# PCB-BI8-SE-C30.net
KiCad netlist of a schematic drawn in EAGLE
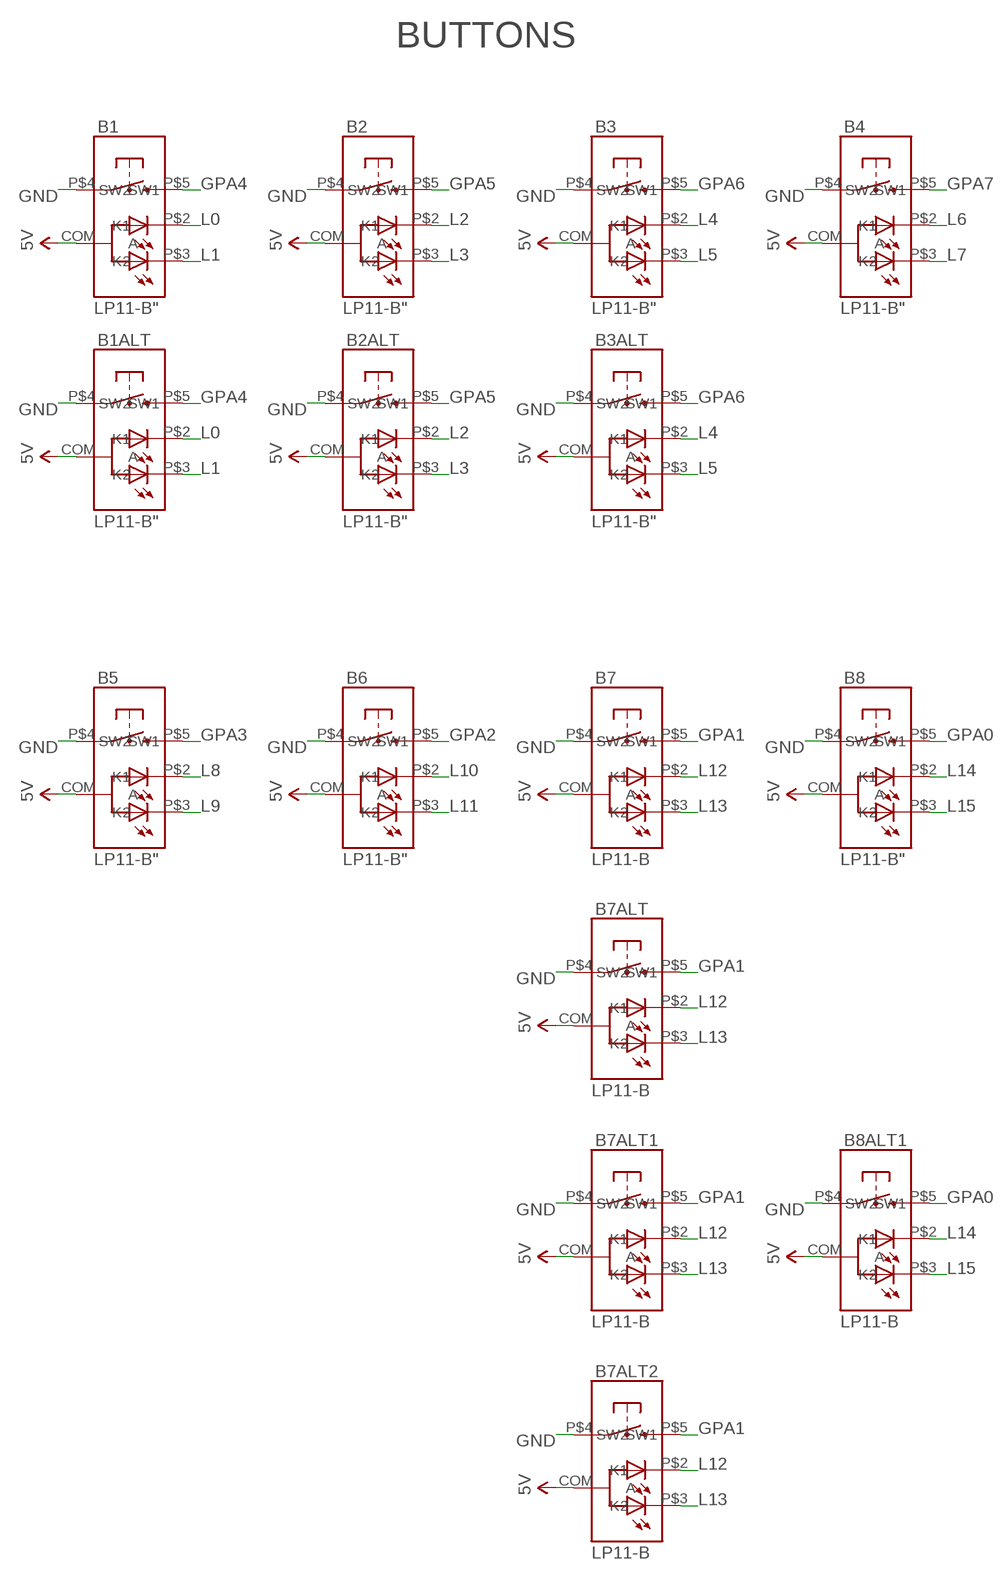
[diagram p0: schematic, sheet 1, part 1 of 2]
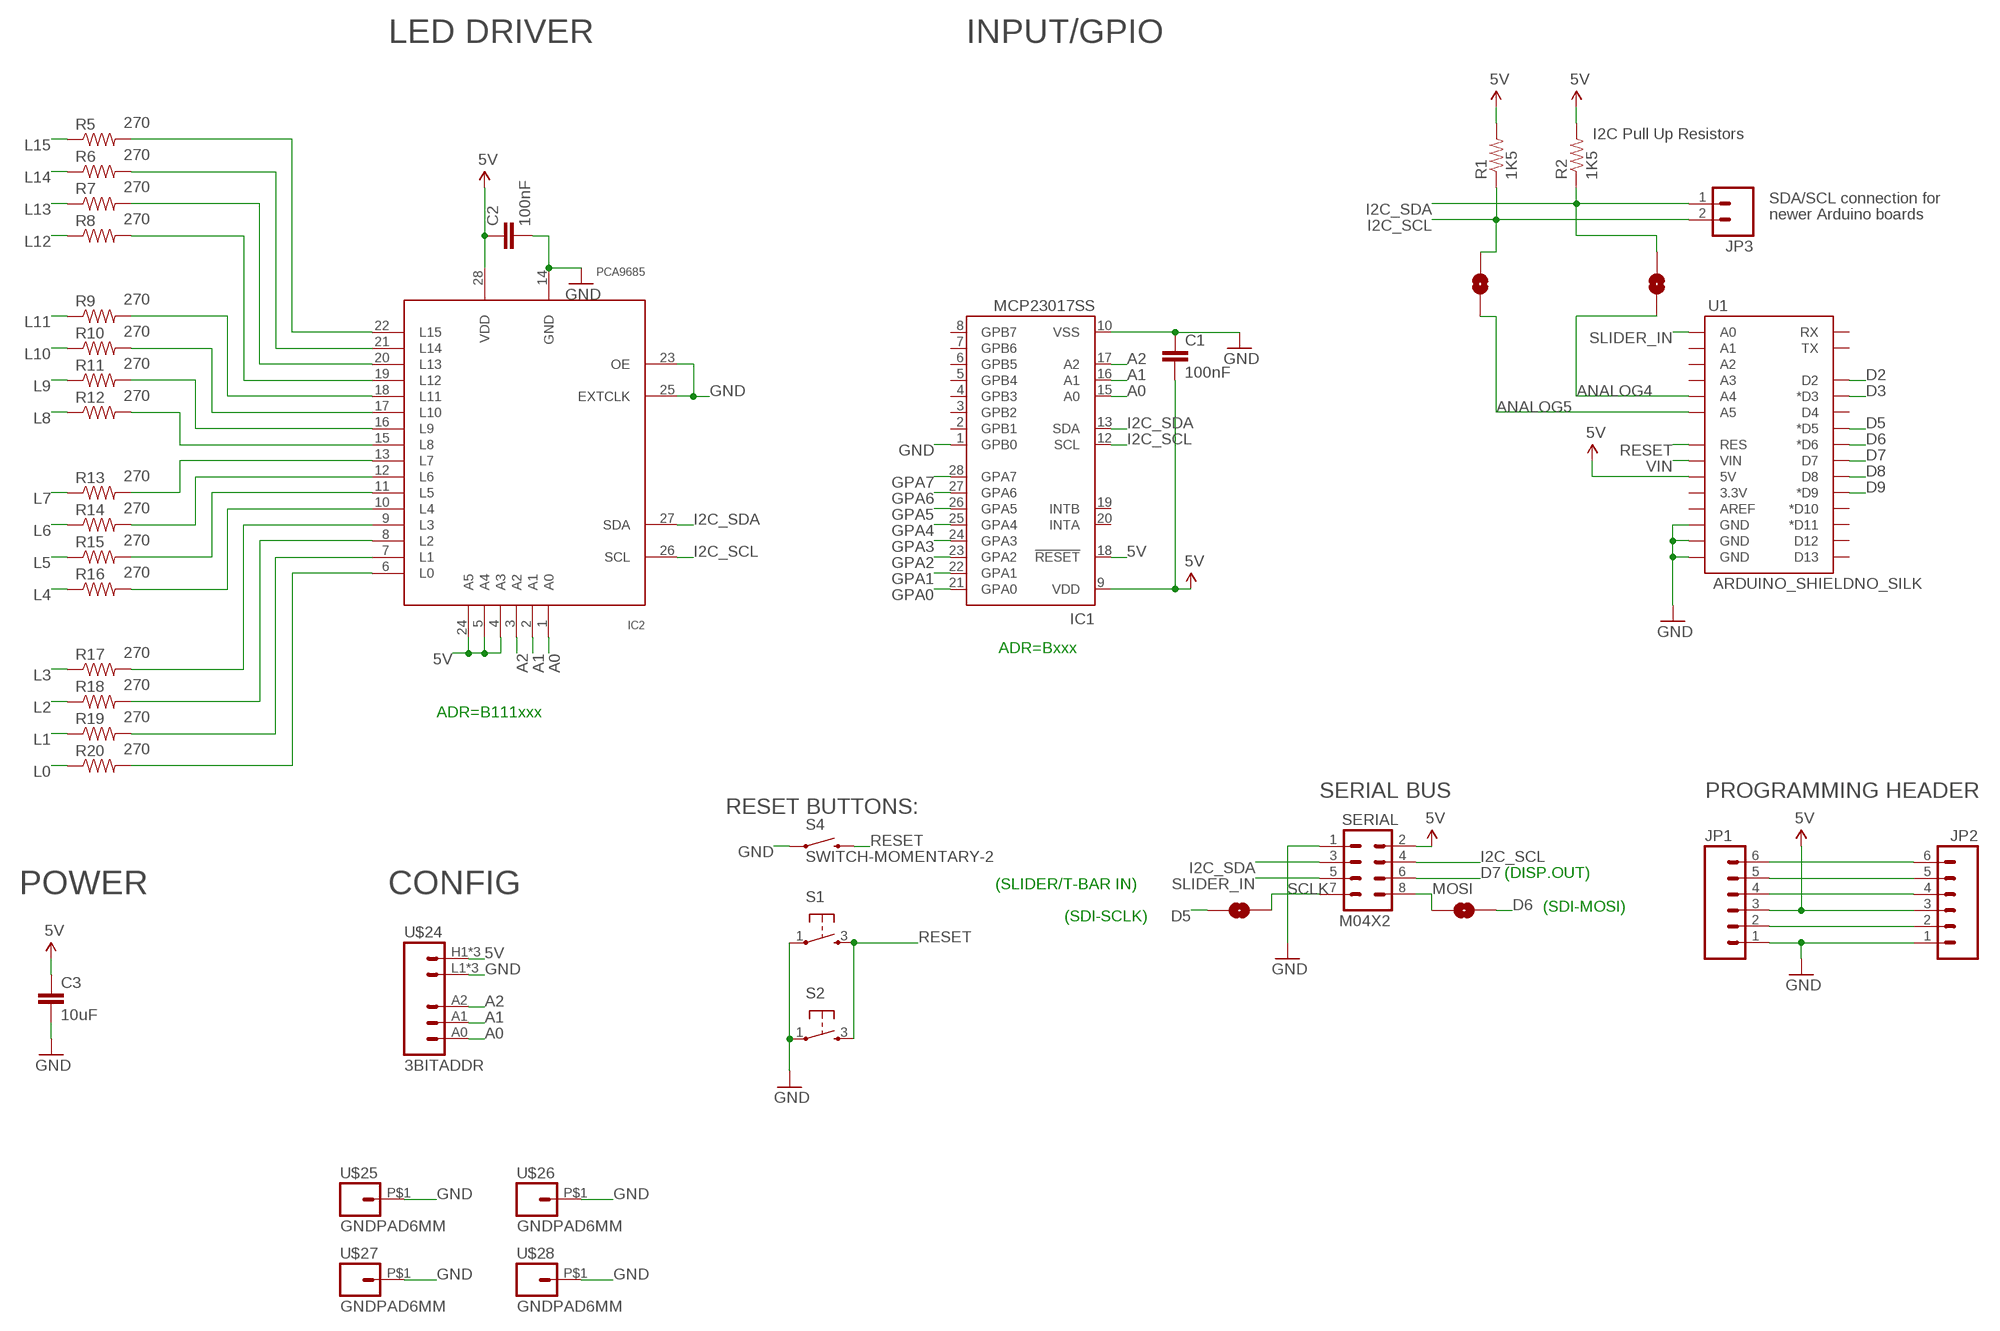
[diagram p1: schematic, sheet 1, part 2 of 2]

(export (version "E")
  (design (tool "Eeschema 10.0.6"))
  (components
    (comp (ref "B1")
      (value "LP11-B\"")
      (footprint "eagle-import:LP11")
      (libsource (lib "eagle-import") (part "LP11-B{dblquote}"))
    )
    (comp (ref "B1ALT")
      (value "LP11-B\"")
      (footprint "eagle-import:LP11")
      (libsource (lib "eagle-import") (part "LP11-B{dblquote}"))
    )
    (comp (ref "B2")
      (value "LP11-B\"")
      (footprint "eagle-import:LP11")
      (libsource (lib "eagle-import") (part "LP11-B{dblquote}"))
    )
    (comp (ref "B2ALT")
      (value "LP11-B\"")
      (footprint "eagle-import:LP11")
      (libsource (lib "eagle-import") (part "LP11-B{dblquote}"))
    )
    (comp (ref "B3")
      (value "LP11-B\"")
      (footprint "eagle-import:LP11")
      (libsource (lib "eagle-import") (part "LP11-B{dblquote}"))
    )
    (comp (ref "B3ALT")
      (value "LP11-B\"")
      (footprint "eagle-import:LP11")
      (libsource (lib "eagle-import") (part "LP11-B{dblquote}"))
    )
    (comp (ref "B4")
      (value "LP11-B\"")
      (footprint "eagle-import:LP11")
      (libsource (lib "eagle-import") (part "LP11-B{dblquote}"))
    )
    (comp (ref "B5")
      (value "LP11-B\"")
      (footprint "eagle-import:LP11")
      (libsource (lib "eagle-import") (part "LP11-B{dblquote}"))
    )
    (comp (ref "B6")
      (value "LP11-B\"")
      (footprint "eagle-import:LP11")
      (libsource (lib "eagle-import") (part "LP11-B{dblquote}"))
    )
    (comp (ref "B7")
      (value "LP11-B")
      (footprint "eagle-import:LP11_NOFIXHOLES")
      (libsource (lib "eagle-import") (part "LP11-B"))
    )
    (comp (ref "B7ALT")
      (value "LP11-B")
      (footprint "eagle-import:LP11_NOFIXHOLES")
      (libsource (lib "eagle-import") (part "LP11-B"))
    )
    (comp (ref "B7ALT1")
      (value "LP11-B")
      (footprint "eagle-import:LP11_NOFIXHOLES")
      (libsource (lib "eagle-import") (part "LP11-B"))
    )
    (comp (ref "B7ALT2")
      (value "LP11-B")
      (footprint "eagle-import:LP11_NOFIXHOLES")
      (libsource (lib "eagle-import") (part "LP11-B"))
    )
    (comp (ref "B8")
      (value "LP11-B\"")
      (footprint "eagle-import:LP11")
      (libsource (lib "eagle-import") (part "LP11-B{dblquote}"))
    )
    (comp (ref "B8ALT1")
      (value "LP11-B")
      (footprint "eagle-import:LP11_NOFIXHOLES")
      (libsource (lib "eagle-import") (part "LP11-B"))
    )
    (comp (ref "C1")
      (value "100nF")
      (footprint "eagle-import:0603-CAP")
      (libsource (lib "eagle-import") (part "CAP0603-CAP"))
    )
    (comp (ref "C2")
      (value "100nF")
      (footprint "eagle-import:0603-CAP")
      (libsource (lib "eagle-import") (part "CAP0603-CAP"))
    )
    (comp (ref "C3")
      (value "10uF")
      (footprint "eagle-import:0805")
      (libsource (lib "eagle-import") (part "CAP0805"))
    )
    (comp (ref "IC1")
      (value "MCP23017SS")
      (footprint "eagle-import:SSOP28")
      (fields
        (field (name "MF") "MICROCHIP")
        (field (name "MPN") "MCP23017-E/SS")
        (field (name "MPN_1") "MCP23017-E/SS")
        (field (name "OC_FARNELL") "1467674")
        (field (name "OC_NEWARK") "31K2960")
      )
      (libsource (lib "eagle-import") (part "MCP23017SS"))
    )
    (comp (ref "IC2")
      (value "PCA9685")
      (footprint "eagle-import:TSSOP28")
      (libsource (lib "eagle-import") (part "PCA9685"))
    )
    (comp (ref "JP1")
      (value "M06POLAR")
      (footprint "eagle-import:MOLEX-1X6")
      (libsource (lib "eagle-import") (part "M06POLAR"))
    )
    (comp (ref "JP2")
      (value "M06POLAR")
      (footprint "eagle-import:MOLEX-1X6")
      (libsource (lib "eagle-import") (part "M06POLAR"))
    )
    (comp (ref "JP3")
      (value "M02PTH")
      (footprint "eagle-import:1X02")
      (libsource (lib "eagle-import") (part "M02PTH"))
    )
    (comp (ref "MOSI->D6")
      (value "SOLDERJUMPERNC")
      (footprint "eagle-import:SJ_2S")
      (libsource (lib "eagle-import") (part "SOLDERJUMPERNC"))
    )
    (comp (ref "R1")
      (value "1K5")
      (footprint "eagle-import:0603-RES")
      (libsource (lib "eagle-import") (part "RESISTOR0603-RES"))
    )
    (comp (ref "R2")
      (value "1K5")
      (footprint "eagle-import:0603-RES")
      (libsource (lib "eagle-import") (part "RESISTOR0603-RES"))
    )
    (comp (ref "R5")
      (value "270")
      (footprint "eagle-import:0603-RES")
      (libsource (lib "eagle-import") (part "RESISTOR0603-RES"))
    )
    (comp (ref "R6")
      (value "270")
      (footprint "eagle-import:0603-RES")
      (libsource (lib "eagle-import") (part "RESISTOR0603-RES"))
    )
    (comp (ref "R7")
      (value "270")
      (footprint "eagle-import:0603-RES")
      (libsource (lib "eagle-import") (part "RESISTOR0603-RES"))
    )
    (comp (ref "R8")
      (value "270")
      (footprint "eagle-import:0603-RES")
      (libsource (lib "eagle-import") (part "RESISTOR0603-RES"))
    )
    (comp (ref "R9")
      (value "270")
      (footprint "eagle-import:0603-RES")
      (libsource (lib "eagle-import") (part "RESISTOR0603-RES"))
    )
    (comp (ref "R10")
      (value "270")
      (footprint "eagle-import:0603-RES")
      (libsource (lib "eagle-import") (part "RESISTOR0603-RES"))
    )
    (comp (ref "R11")
      (value "270")
      (footprint "eagle-import:0603-RES")
      (libsource (lib "eagle-import") (part "RESISTOR0603-RES"))
    )
    (comp (ref "R12")
      (value "270")
      (footprint "eagle-import:0603-RES")
      (libsource (lib "eagle-import") (part "RESISTOR0603-RES"))
    )
    (comp (ref "R13")
      (value "270")
      (footprint "eagle-import:0603-RES")
      (libsource (lib "eagle-import") (part "RESISTOR0603-RES"))
    )
    (comp (ref "R14")
      (value "270")
      (footprint "eagle-import:0603-RES")
      (libsource (lib "eagle-import") (part "RESISTOR0603-RES"))
    )
    (comp (ref "R15")
      (value "270")
      (footprint "eagle-import:0603-RES")
      (libsource (lib "eagle-import") (part "RESISTOR0603-RES"))
    )
    (comp (ref "R16")
      (value "270")
      (footprint "eagle-import:0603-RES")
      (libsource (lib "eagle-import") (part "RESISTOR0603-RES"))
    )
    (comp (ref "R17")
      (value "270")
      (footprint "eagle-import:0603-RES")
      (libsource (lib "eagle-import") (part "RESISTOR0603-RES"))
    )
    (comp (ref "R18")
      (value "270")
      (footprint "eagle-import:0603-RES")
      (libsource (lib "eagle-import") (part "RESISTOR0603-RES"))
    )
    (comp (ref "R19")
      (value "270")
      (footprint "eagle-import:0603-RES")
      (libsource (lib "eagle-import") (part "RESISTOR0603-RES"))
    )
    (comp (ref "R20")
      (value "270")
      (footprint "eagle-import:0603-RES")
      (libsource (lib "eagle-import") (part "RESISTOR0603-RES"))
    )
    (comp (ref "S1")
      (value "TAC_SWITCH")
      (footprint "eagle-import:PUSHBUTTON")
      (libsource (lib "eagle-import") (part "TAC_SWITCH"))
    )
    (comp (ref "S2")
      (value "TAC_SWITCH")
      (footprint "eagle-import:PUSHBUTTON")
      (libsource (lib "eagle-import") (part "TAC_SWITCH"))
    )
    (comp (ref "S3->A2")
      (value "SOLDERJUMPERNC")
      (footprint "eagle-import:SJ_2S")
      (libsource (lib "eagle-import") (part "SOLDERJUMPERNC"))
    )
    (comp (ref "S3->A3")
      (value "SOLDERJUMPERNC")
      (footprint "eagle-import:SJ_2S")
      (libsource (lib "eagle-import") (part "SOLDERJUMPERNC"))
    )
    (comp (ref "S4")
      (value "SWITCH-MOMENTARY-2")
      (footprint "eagle-import:TACTILE_SWITCH_TALL")
      (libsource (lib "eagle-import") (part "SWITCH-MOMENTARY-2"))
    )
    (comp (ref "SCLK->D5")
      (value "SOLDERJUMPERNC")
      (footprint "eagle-import:SJ_2S")
      (libsource (lib "eagle-import") (part "SOLDERJUMPERNC"))
    )
    (comp (ref "SERIAL")
      (value "M04X2")
      (footprint "eagle-import:2X4")
      (libsource (lib "eagle-import") (part "M04X2"))
    )
    (comp (ref "U$24")
      (value "3BITADDR")
      (footprint "eagle-import:3BITADDR")
      (libsource (lib "eagle-import") (part "3BITADDR"))
    )
    (comp (ref "U$25")
      (value "GNDPAD6MM")
      (footprint "eagle-import:3.2MMPAD6MM")
      (libsource (lib "eagle-import") (part "GNDPAD6MM"))
    )
    (comp (ref "U$26")
      (value "GNDPAD6MM")
      (footprint "eagle-import:3.2MMPAD6MM")
      (libsource (lib "eagle-import") (part "GNDPAD6MM"))
    )
    (comp (ref "U$27")
      (value "GNDPAD6MM")
      (footprint "eagle-import:3.2MMPAD6MM")
      (libsource (lib "eagle-import") (part "GNDPAD6MM"))
    )
    (comp (ref "U$28")
      (value "GNDPAD6MM")
      (footprint "eagle-import:3.2MMPAD6MM")
      (libsource (lib "eagle-import") (part "GNDPAD6MM"))
    )
    (comp (ref "U1")
      (value "ARDUINO_SHIELDNO_SILK")
      (footprint "eagle-import:DUEMILANOVE_VIAS")
      (libsource (lib "eagle-import") (part "ARDUINO_SHIELDNO_SILK"))
    )
  )
  (nets
    (net (code "1") (name "/A0") (class "Default")
      (node (ref "IC1") (pin "15") (pinfunction "A0_15") (pintype "input"))
      (node (ref "IC2") (pin "1") (pinfunction "A0_1") (pintype "input"))
      (node (ref "U$24") (pin "A0") (pinfunction "A0_A0") (pintype "passive"))
    )
    (net (code "2") (name "/A1") (class "Default")
      (node (ref "IC1") (pin "16") (pinfunction "A1_16") (pintype "input"))
      (node (ref "IC2") (pin "2") (pinfunction "A1_2") (pintype "input"))
      (node (ref "U$24") (pin "A1") (pinfunction "A1_A1") (pintype "passive"))
    )
    (net (code "3") (name "/A2") (class "Default")
      (node (ref "IC1") (pin "17") (pinfunction "A2_17") (pintype "input"))
      (node (ref "IC2") (pin "3") (pinfunction "A2_3") (pintype "input"))
      (node (ref "U$24") (pin "A2") (pinfunction "A2_A2") (pintype "passive"))
    )
    (net (code "4") (name "/ANALOG4") (class "Default")
      (node (ref "S3->A3") (pin "2") (pinfunction "2_2") (pintype "passive"))
      (node (ref "U1") (pin "A4") (pinfunction "A4_A4") (pintype "bidirectional"))
    )
    (net (code "5") (name "/ANALOG5") (class "Default")
      (node (ref "S3->A2") (pin "2") (pinfunction "2_2") (pintype "passive"))
      (node (ref "U1") (pin "A5") (pinfunction "A5_A5") (pintype "bidirectional"))
    )
    (net (code "6") (name "/D2") (class "Default")
      (node (ref "U1") (pin "D2") (pinfunction "D2_D2") (pintype "bidirectional"))
    )
    (net (code "7") (name "/D3") (class "Default")
      (node (ref "U1") (pin "D3") (pinfunction "*D3_D3") (pintype "bidirectional"))
    )
    (net (code "8") (name "/D5") (class "Default")
      (node (ref "SCLK->D5") (pin "1") (pinfunction "1_1") (pintype "passive"))
      (node (ref "U1") (pin "D5") (pinfunction "*D5_D5") (pintype "bidirectional"))
    )
    (net (code "9") (name "/D6") (class "Default")
      (node (ref "MOSI->D6") (pin "2") (pinfunction "2_2") (pintype "passive"))
      (node (ref "U1") (pin "D6") (pinfunction "*D6_D6") (pintype "bidirectional"))
    )
    (net (code "10") (name "/D7") (class "Default")
      (node (ref "SERIAL") (pin "6") (pinfunction "6_6") (pintype "passive"))
      (node (ref "U1") (pin "D7") (pinfunction "D7_D7") (pintype "bidirectional"))
    )
    (net (code "11") (name "/D8") (class "Default")
      (node (ref "U1") (pin "D8") (pinfunction "D8_D8") (pintype "bidirectional"))
    )
    (net (code "12") (name "/D9") (class "Default")
      (node (ref "U1") (pin "D9") (pinfunction "*D9_D9") (pintype "bidirectional"))
    )
    (net (code "13") (name "/GPA0") (class "Default")
      (node (ref "B8") (pin "P$5") (pinfunction "SW2_P$5") (pintype "bidirectional"))
      (node (ref "B8ALT1") (pin "P$5") (pinfunction "SW2_P$5") (pintype "bidirectional"))
      (node (ref "IC1") (pin "21") (pinfunction "GPA0_21") (pintype "bidirectional"))
    )
    (net (code "14") (name "/GPA1") (class "Default")
      (node (ref "B7") (pin "P$5") (pinfunction "SW2_P$5") (pintype "bidirectional"))
      (node (ref "B7ALT") (pin "P$5") (pinfunction "SW2_P$5") (pintype "bidirectional"))
      (node (ref "B7ALT1") (pin "P$5") (pinfunction "SW2_P$5") (pintype "bidirectional"))
      (node (ref "B7ALT2") (pin "P$5") (pinfunction "SW2_P$5") (pintype "bidirectional"))
      (node (ref "IC1") (pin "22") (pinfunction "GPA1_22") (pintype "bidirectional"))
    )
    (net (code "15") (name "/GPA2") (class "Default")
      (node (ref "B6") (pin "P$5") (pinfunction "SW2_P$5") (pintype "bidirectional"))
      (node (ref "IC1") (pin "23") (pinfunction "GPA2_23") (pintype "bidirectional"))
    )
    (net (code "16") (name "/GPA3") (class "Default")
      (node (ref "B5") (pin "P$5") (pinfunction "SW2_P$5") (pintype "bidirectional"))
      (node (ref "IC1") (pin "24") (pinfunction "GPA3_24") (pintype "bidirectional"))
    )
    (net (code "17") (name "/GPA4") (class "Default")
      (node (ref "B1") (pin "P$5") (pinfunction "SW2_P$5") (pintype "bidirectional"))
      (node (ref "B1ALT") (pin "P$5") (pinfunction "SW2_P$5") (pintype "bidirectional"))
      (node (ref "IC1") (pin "25") (pinfunction "GPA4_25") (pintype "bidirectional"))
    )
    (net (code "18") (name "/GPA5") (class "Default")
      (node (ref "B2") (pin "P$5") (pinfunction "SW2_P$5") (pintype "bidirectional"))
      (node (ref "B2ALT") (pin "P$5") (pinfunction "SW2_P$5") (pintype "bidirectional"))
      (node (ref "IC1") (pin "26") (pinfunction "GPA5_26") (pintype "bidirectional"))
    )
    (net (code "19") (name "/GPA6") (class "Default")
      (node (ref "B3") (pin "P$5") (pinfunction "SW2_P$5") (pintype "bidirectional"))
      (node (ref "B3ALT") (pin "P$5") (pinfunction "SW2_P$5") (pintype "bidirectional"))
      (node (ref "IC1") (pin "27") (pinfunction "GPA6_27") (pintype "bidirectional"))
    )
    (net (code "20") (name "/GPA7") (class "Default")
      (node (ref "B4") (pin "P$5") (pinfunction "SW2_P$5") (pintype "bidirectional"))
      (node (ref "IC1") (pin "28") (pinfunction "GPA7_28") (pintype "bidirectional"))
    )
    (net (code "21") (name "/I2C_SCL") (class "Default")
      (node (ref "IC1") (pin "12") (pinfunction "SCL_12") (pintype "input"))
      (node (ref "IC2") (pin "26") (pinfunction "SCL_26") (pintype "input"))
      (node (ref "JP3") (pin "2") (pinfunction "2_2") (pintype "passive"))
      (node (ref "R1") (pin "1") (pinfunction "1_1") (pintype "passive"))
      (node (ref "S3->A2") (pin "1") (pinfunction "1_1") (pintype "passive"))
      (node (ref "SERIAL") (pin "4") (pinfunction "4_4") (pintype "passive"))
    )
    (net (code "22") (name "/I2C_SDA") (class "Default")
      (node (ref "IC1") (pin "13") (pinfunction "SDA_13") (pintype "bidirectional"))
      (node (ref "IC2") (pin "27") (pinfunction "SDA_27") (pintype "input"))
      (node (ref "JP3") (pin "1") (pinfunction "1_1") (pintype "passive"))
      (node (ref "R2") (pin "1") (pinfunction "1_1") (pintype "passive"))
      (node (ref "S3->A3") (pin "1") (pinfunction "1_1") (pintype "passive"))
      (node (ref "SERIAL") (pin "3") (pinfunction "3_3") (pintype "passive"))
    )
    (net (code "23") (name "/L0") (class "Default")
      (node (ref "B1") (pin "P$2") (pinfunction "K1_P$2") (pintype "bidirectional"))
      (node (ref "B1ALT") (pin "P$2") (pinfunction "K1_P$2") (pintype "bidirectional"))
      (node (ref "R20") (pin "1") (pinfunction "1_1") (pintype "passive"))
    )
    (net (code "24") (name "/L1") (class "Default")
      (node (ref "B1") (pin "P$3") (pinfunction "K2_P$3") (pintype "bidirectional"))
      (node (ref "B1ALT") (pin "P$3") (pinfunction "K2_P$3") (pintype "bidirectional"))
      (node (ref "R19") (pin "1") (pinfunction "1_1") (pintype "passive"))
    )
    (net (code "25") (name "/L2") (class "Default")
      (node (ref "B2") (pin "P$2") (pinfunction "K1_P$2") (pintype "bidirectional"))
      (node (ref "B2ALT") (pin "P$2") (pinfunction "K1_P$2") (pintype "bidirectional"))
      (node (ref "R18") (pin "1") (pinfunction "1_1") (pintype "passive"))
    )
    (net (code "26") (name "/L3") (class "Default")
      (node (ref "B2") (pin "P$3") (pinfunction "K2_P$3") (pintype "bidirectional"))
      (node (ref "B2ALT") (pin "P$3") (pinfunction "K2_P$3") (pintype "bidirectional"))
      (node (ref "R17") (pin "1") (pinfunction "1_1") (pintype "passive"))
    )
    (net (code "27") (name "/L4") (class "Default")
      (node (ref "B3") (pin "P$2") (pinfunction "K1_P$2") (pintype "bidirectional"))
      (node (ref "B3ALT") (pin "P$2") (pinfunction "K1_P$2") (pintype "bidirectional"))
      (node (ref "R16") (pin "1") (pinfunction "1_1") (pintype "passive"))
    )
    (net (code "28") (name "/L5") (class "Default")
      (node (ref "B3") (pin "P$3") (pinfunction "K2_P$3") (pintype "bidirectional"))
      (node (ref "B3ALT") (pin "P$3") (pinfunction "K2_P$3") (pintype "bidirectional"))
      (node (ref "R15") (pin "1") (pinfunction "1_1") (pintype "passive"))
    )
    (net (code "29") (name "/L6") (class "Default")
      (node (ref "B4") (pin "P$2") (pinfunction "K1_P$2") (pintype "bidirectional"))
      (node (ref "R14") (pin "1") (pinfunction "1_1") (pintype "passive"))
    )
    (net (code "30") (name "/L7") (class "Default")
      (node (ref "B4") (pin "P$3") (pinfunction "K2_P$3") (pintype "bidirectional"))
      (node (ref "R13") (pin "1") (pinfunction "1_1") (pintype "passive"))
    )
    (net (code "31") (name "/L8") (class "Default")
      (node (ref "B5") (pin "P$2") (pinfunction "K1_P$2") (pintype "bidirectional"))
      (node (ref "R12") (pin "1") (pinfunction "1_1") (pintype "passive"))
    )
    (net (code "32") (name "/L9") (class "Default")
      (node (ref "B5") (pin "P$3") (pinfunction "K2_P$3") (pintype "bidirectional"))
      (node (ref "R11") (pin "1") (pinfunction "1_1") (pintype "passive"))
    )
    (net (code "33") (name "/L10") (class "Default")
      (node (ref "B6") (pin "P$2") (pinfunction "K1_P$2") (pintype "bidirectional"))
      (node (ref "R10") (pin "1") (pinfunction "1_1") (pintype "passive"))
    )
    (net (code "34") (name "/L11") (class "Default")
      (node (ref "B6") (pin "P$3") (pinfunction "K2_P$3") (pintype "bidirectional"))
      (node (ref "R9") (pin "1") (pinfunction "1_1") (pintype "passive"))
    )
    (net (code "35") (name "/L12") (class "Default")
      (node (ref "B7") (pin "P$2") (pinfunction "K1_P$2") (pintype "bidirectional"))
      (node (ref "B7ALT") (pin "P$2") (pinfunction "K1_P$2") (pintype "bidirectional"))
      (node (ref "B7ALT1") (pin "P$2") (pinfunction "K1_P$2") (pintype "bidirectional"))
      (node (ref "B7ALT2") (pin "P$2") (pinfunction "K1_P$2") (pintype "bidirectional"))
      (node (ref "R8") (pin "1") (pinfunction "1_1") (pintype "passive"))
    )
    (net (code "36") (name "/L13") (class "Default")
      (node (ref "B7") (pin "P$3") (pinfunction "K2_P$3") (pintype "bidirectional"))
      (node (ref "B7ALT") (pin "P$3") (pinfunction "K2_P$3") (pintype "bidirectional"))
      (node (ref "B7ALT1") (pin "P$3") (pinfunction "K2_P$3") (pintype "bidirectional"))
      (node (ref "B7ALT2") (pin "P$3") (pinfunction "K2_P$3") (pintype "bidirectional"))
      (node (ref "R7") (pin "1") (pinfunction "1_1") (pintype "passive"))
    )
    (net (code "37") (name "/L14") (class "Default")
      (node (ref "B8") (pin "P$2") (pinfunction "K1_P$2") (pintype "bidirectional"))
      (node (ref "B8ALT1") (pin "P$2") (pinfunction "K1_P$2") (pintype "bidirectional"))
      (node (ref "R6") (pin "1") (pinfunction "1_1") (pintype "passive"))
    )
    (net (code "38") (name "/L15") (class "Default")
      (node (ref "B8") (pin "P$3") (pinfunction "K2_P$3") (pintype "bidirectional"))
      (node (ref "B8ALT1") (pin "P$3") (pinfunction "K2_P$3") (pintype "bidirectional"))
      (node (ref "R5") (pin "1") (pinfunction "1_1") (pintype "passive"))
    )
    (net (code "39") (name "/MOSI") (class "Default")
      (node (ref "MOSI->D6") (pin "1") (pinfunction "1_1") (pintype "passive"))
      (node (ref "SERIAL") (pin "8") (pinfunction "8_8") (pintype "passive"))
    )
    (net (code "40") (name "/RESET") (class "Default")
      (node (ref "S1") (pin "3") (pinfunction "3_3") (pintype "passive"))
      (node (ref "S2") (pin "3") (pinfunction "3_3") (pintype "passive"))
      (node (ref "S4") (pin "B2") (pinfunction "2_B2") (pintype "passive"))
      (node (ref "U1") (pin "RES") (pinfunction "RES_RES") (pintype "bidirectional"))
    )
    (net (code "41") (name "/SCLK") (class "Default")
      (node (ref "SCLK->D5") (pin "2") (pinfunction "2_2") (pintype "passive"))
      (node (ref "SERIAL") (pin "7") (pinfunction "7_7") (pintype "passive"))
    )
    (net (code "42") (name "/SLIDER_IN") (class "Default")
      (node (ref "SERIAL") (pin "5") (pinfunction "5_5") (pintype "passive"))
      (node (ref "U1") (pin "A0") (pinfunction "A0_A0") (pintype "bidirectional"))
    )
    (net (code "43") (name "/VIN") (class "Default")
      (node (ref "U1") (pin "VIN") (pinfunction "VIN_VIN") (pintype "bidirectional"))
    )
    (net (code "44") (name "5V") (class "Default")
      (node (ref "B1") (pin "COM") (pinfunction "A_COM") (pintype "bidirectional"))
      (node (ref "B1ALT") (pin "COM") (pinfunction "A_COM") (pintype "bidirectional"))
      (node (ref "B2") (pin "COM") (pinfunction "A_COM") (pintype "bidirectional"))
      (node (ref "B2ALT") (pin "COM") (pinfunction "A_COM") (pintype "bidirectional"))
      (node (ref "B3") (pin "COM") (pinfunction "A_COM") (pintype "bidirectional"))
      (node (ref "B3ALT") (pin "COM") (pinfunction "A_COM") (pintype "bidirectional"))
      (node (ref "B4") (pin "COM") (pinfunction "A_COM") (pintype "bidirectional"))
      (node (ref "B5") (pin "COM") (pinfunction "A_COM") (pintype "bidirectional"))
      (node (ref "B6") (pin "COM") (pinfunction "A_COM") (pintype "bidirectional"))
      (node (ref "B7") (pin "COM") (pinfunction "A_COM") (pintype "bidirectional"))
      (node (ref "B7ALT") (pin "COM") (pinfunction "A_COM") (pintype "bidirectional"))
      (node (ref "B7ALT1") (pin "COM") (pinfunction "A_COM") (pintype "bidirectional"))
      (node (ref "B7ALT2") (pin "COM") (pinfunction "A_COM") (pintype "bidirectional"))
      (node (ref "B8") (pin "COM") (pinfunction "A_COM") (pintype "bidirectional"))
      (node (ref "B8ALT1") (pin "COM") (pinfunction "A_COM") (pintype "bidirectional"))
      (node (ref "C1") (pin "2") (pinfunction "2_2") (pintype "passive"))
      (node (ref "C2") (pin "1") (pinfunction "1_1") (pintype "passive"))
      (node (ref "C3") (pin "1") (pinfunction "1_1") (pintype "passive"))
      (node (ref "IC1") (pin "18") (pinfunction "~{RESET}_18") (pintype "input"))
      (node (ref "IC1") (pin "9") (pinfunction "VDD_9") (pintype "power_in"))
      (node (ref "IC2") (pin "24") (pinfunction "A5_24") (pintype "input"))
      (node (ref "IC2") (pin "28") (pinfunction "VDD_28") (pintype "power_in"))
      (node (ref "IC2") (pin "4") (pinfunction "A3_4") (pintype "input"))
      (node (ref "IC2") (pin "5") (pinfunction "A4_5") (pintype "input"))
      (node (ref "JP1") (pin "3") (pinfunction "3_3") (pintype "passive"))
      (node (ref "JP2") (pin "3") (pinfunction "3_3") (pintype "passive"))
      (node (ref "R1") (pin "2") (pinfunction "2_2") (pintype "passive"))
      (node (ref "R2") (pin "2") (pinfunction "2_2") (pintype "passive"))
      (node (ref "SERIAL") (pin "2") (pinfunction "2_2") (pintype "passive"))
      (node (ref "U$24") (pin "H1") (pinfunction "VCC_H1") (pintype "passive"))
      (node (ref "U$24") (pin "H2") (pinfunction "VCC_H2") (pintype "passive"))
      (node (ref "U$24") (pin "H3") (pinfunction "VCC_H3") (pintype "passive"))
      (node (ref "U1") (pin "5V") (pinfunction "5V_5V") (pintype "bidirectional"))
    )
    (net (code "45") (name "GND") (class "Default")
      (node (ref "B1") (pin "P$4") (pinfunction "SW1_P$4") (pintype "bidirectional"))
      (node (ref "B1ALT") (pin "P$4") (pinfunction "SW1_P$4") (pintype "bidirectional"))
      (node (ref "B2") (pin "P$4") (pinfunction "SW1_P$4") (pintype "bidirectional"))
      (node (ref "B2ALT") (pin "P$4") (pinfunction "SW1_P$4") (pintype "bidirectional"))
      (node (ref "B3") (pin "P$4") (pinfunction "SW1_P$4") (pintype "bidirectional"))
      (node (ref "B3ALT") (pin "P$4") (pinfunction "SW1_P$4") (pintype "bidirectional"))
      (node (ref "B4") (pin "P$4") (pinfunction "SW1_P$4") (pintype "bidirectional"))
      (node (ref "B5") (pin "P$4") (pinfunction "SW1_P$4") (pintype "bidirectional"))
      (node (ref "B6") (pin "P$4") (pinfunction "SW1_P$4") (pintype "bidirectional"))
      (node (ref "B7") (pin "P$4") (pinfunction "SW1_P$4") (pintype "bidirectional"))
      (node (ref "B7ALT") (pin "P$4") (pinfunction "SW1_P$4") (pintype "bidirectional"))
      (node (ref "B7ALT1") (pin "P$4") (pinfunction "SW1_P$4") (pintype "bidirectional"))
      (node (ref "B7ALT2") (pin "P$4") (pinfunction "SW1_P$4") (pintype "bidirectional"))
      (node (ref "B8") (pin "P$4") (pinfunction "SW1_P$4") (pintype "bidirectional"))
      (node (ref "B8ALT1") (pin "P$4") (pinfunction "SW1_P$4") (pintype "bidirectional"))
      (node (ref "C1") (pin "1") (pinfunction "1_1") (pintype "passive"))
      (node (ref "C2") (pin "2") (pinfunction "2_2") (pintype "passive"))
      (node (ref "C3") (pin "2") (pinfunction "2_2") (pintype "passive"))
      (node (ref "IC1") (pin "1") (pinfunction "GPB0_1") (pintype "bidirectional"))
      (node (ref "IC1") (pin "10") (pinfunction "VSS_10") (pintype "power_in"))
      (node (ref "IC2") (pin "14") (pinfunction "GND_14") (pintype "power_in"))
      (node (ref "IC2") (pin "23") (pinfunction "OE_23") (pintype "input"))
      (node (ref "IC2") (pin "25") (pinfunction "EXTCLK_25") (pintype "input"))
      (node (ref "JP1") (pin "1") (pinfunction "1_1") (pintype "passive"))
      (node (ref "JP2") (pin "1") (pinfunction "1_1") (pintype "passive"))
      (node (ref "S1") (pin "1") (pinfunction "1_1") (pintype "passive"))
      (node (ref "S2") (pin "1") (pinfunction "1_1") (pintype "passive"))
      (node (ref "S4") (pin "A2") (pinfunction "1_A2") (pintype "passive"))
      (node (ref "SERIAL") (pin "1") (pinfunction "1_1") (pintype "passive"))
      (node (ref "U$24") (pin "L1") (pinfunction "GND_L1") (pintype "passive"))
      (node (ref "U$24") (pin "L2") (pinfunction "GND_L2") (pintype "passive"))
      (node (ref "U$24") (pin "L3") (pinfunction "GND_L3") (pintype "passive"))
      (node (ref "U$25") (pin "P$1") (pinfunction "1_P$1") (pintype "passive"))
      (node (ref "U$26") (pin "P$1") (pinfunction "1_P$1") (pintype "passive"))
      (node (ref "U$27") (pin "P$1") (pinfunction "1_P$1") (pintype "passive"))
      (node (ref "U$28") (pin "P$1") (pinfunction "1_P$1") (pintype "passive"))
      (node (ref "U1") (pin "GND@0") (pinfunction "GND_GND@0") (pintype "bidirectional"))
      (node (ref "U1") (pin "GND@1") (pinfunction "GND_GND@1") (pintype "bidirectional"))
      (node (ref "U1") (pin "GND@2") (pinfunction "GND_GND@2") (pintype "bidirectional"))
    )
    (net (code "46") (name "Net-(IC2-L0)") (class "Default")
      (node (ref "IC2") (pin "6") (pinfunction "L0_6") (pintype "output"))
      (node (ref "R20") (pin "2") (pinfunction "2_2") (pintype "passive"))
    )
    (net (code "47") (name "Net-(IC2-L1)") (class "Default")
      (node (ref "IC2") (pin "7") (pinfunction "L1_7") (pintype "output"))
      (node (ref "R19") (pin "2") (pinfunction "2_2") (pintype "passive"))
    )
    (net (code "48") (name "Net-(IC2-L2)") (class "Default")
      (node (ref "IC2") (pin "8") (pinfunction "L2_8") (pintype "output"))
      (node (ref "R18") (pin "2") (pinfunction "2_2") (pintype "passive"))
    )
    (net (code "49") (name "Net-(IC2-L3)") (class "Default")
      (node (ref "IC2") (pin "9") (pinfunction "L3_9") (pintype "output"))
      (node (ref "R17") (pin "2") (pinfunction "2_2") (pintype "passive"))
    )
    (net (code "50") (name "Net-(IC2-L4)") (class "Default")
      (node (ref "IC2") (pin "10") (pinfunction "L4_10") (pintype "output"))
      (node (ref "R16") (pin "2") (pinfunction "2_2") (pintype "passive"))
    )
    (net (code "51") (name "Net-(IC2-L5)") (class "Default")
      (node (ref "IC2") (pin "11") (pinfunction "L5_11") (pintype "output"))
      (node (ref "R15") (pin "2") (pinfunction "2_2") (pintype "passive"))
    )
    (net (code "52") (name "Net-(IC2-L6)") (class "Default")
      (node (ref "IC2") (pin "12") (pinfunction "L6_12") (pintype "output"))
      (node (ref "R14") (pin "2") (pinfunction "2_2") (pintype "passive"))
    )
    (net (code "53") (name "Net-(IC2-L7)") (class "Default")
      (node (ref "IC2") (pin "13") (pinfunction "L7_13") (pintype "output"))
      (node (ref "R13") (pin "2") (pinfunction "2_2") (pintype "passive"))
    )
    (net (code "54") (name "Net-(IC2-L8)") (class "Default")
      (node (ref "IC2") (pin "15") (pinfunction "L8_15") (pintype "output"))
      (node (ref "R12") (pin "2") (pinfunction "2_2") (pintype "passive"))
    )
    (net (code "55") (name "Net-(IC2-L9)") (class "Default")
      (node (ref "IC2") (pin "16") (pinfunction "L9_16") (pintype "output"))
      (node (ref "R11") (pin "2") (pinfunction "2_2") (pintype "passive"))
    )
    (net (code "56") (name "Net-(IC2-L10)") (class "Default")
      (node (ref "IC2") (pin "17") (pinfunction "L10_17") (pintype "output"))
      (node (ref "R10") (pin "2") (pinfunction "2_2") (pintype "passive"))
    )
    (net (code "57") (name "Net-(IC2-L11)") (class "Default")
      (node (ref "IC2") (pin "18") (pinfunction "L11_18") (pintype "output"))
      (node (ref "R9") (pin "2") (pinfunction "2_2") (pintype "passive"))
    )
    (net (code "58") (name "Net-(IC2-L12)") (class "Default")
      (node (ref "IC2") (pin "19") (pinfunction "L12_19") (pintype "output"))
      (node (ref "R8") (pin "2") (pinfunction "2_2") (pintype "passive"))
    )
    (net (code "59") (name "Net-(IC2-L13)") (class "Default")
      (node (ref "IC2") (pin "20") (pinfunction "L13_20") (pintype "output"))
      (node (ref "R7") (pin "2") (pinfunction "2_2") (pintype "passive"))
    )
    (net (code "60") (name "Net-(IC2-L14)") (class "Default")
      (node (ref "IC2") (pin "21") (pinfunction "L14_21") (pintype "output"))
      (node (ref "R6") (pin "2") (pinfunction "2_2") (pintype "passive"))
    )
    (net (code "61") (name "Net-(IC2-L15)") (class "Default")
      (node (ref "IC2") (pin "22") (pinfunction "L15_22") (pintype "output"))
      (node (ref "R5") (pin "2") (pinfunction "2_2") (pintype "passive"))
    )
    (net (code "62") (name "Net-(JP1-Pad2)") (class "Default")
      (node (ref "JP1") (pin "2") (pinfunction "2_2") (pintype "passive"))
      (node (ref "JP2") (pin "2") (pinfunction "2_2") (pintype "passive"))
    )
    (net (code "63") (name "Net-(JP1-Pad4)") (class "Default")
      (node (ref "JP1") (pin "4") (pinfunction "4_4") (pintype "passive"))
      (node (ref "JP2") (pin "4") (pinfunction "4_4") (pintype "passive"))
    )
    (net (code "64") (name "Net-(JP1-Pad5)") (class "Default")
      (node (ref "JP1") (pin "5") (pinfunction "5_5") (pintype "passive"))
      (node (ref "JP2") (pin "5") (pinfunction "5_5") (pintype "passive"))
    )
    (net (code "65") (name "Net-(JP1-Pad6)") (class "Default")
      (node (ref "JP1") (pin "6") (pinfunction "6_6") (pintype "passive"))
      (node (ref "JP2") (pin "6") (pinfunction "6_6") (pintype "passive"))
    )
    (net (code "66") (name "unconnected-(IC1-GPB1-Pad2)") (class "Default")
      (node (ref "IC1") (pin "2") (pinfunction "GPB1_2") (pintype "bidirectional"))
    )
    (net (code "67") (name "unconnected-(IC1-GPB2-Pad3)") (class "Default")
      (node (ref "IC1") (pin "3") (pinfunction "GPB2_3") (pintype "bidirectional"))
    )
    (net (code "68") (name "unconnected-(IC1-GPB3-Pad4)") (class "Default")
      (node (ref "IC1") (pin "4") (pinfunction "GPB3_4") (pintype "bidirectional"))
    )
    (net (code "69") (name "unconnected-(IC1-GPB4-Pad5)") (class "Default")
      (node (ref "IC1") (pin "5") (pinfunction "GPB4_5") (pintype "bidirectional"))
    )
    (net (code "70") (name "unconnected-(IC1-GPB5-Pad6)") (class "Default")
      (node (ref "IC1") (pin "6") (pinfunction "GPB5_6") (pintype "bidirectional"))
    )
    (net (code "71") (name "unconnected-(IC1-GPB6-Pad7)") (class "Default")
      (node (ref "IC1") (pin "7") (pinfunction "GPB6_7") (pintype "bidirectional"))
    )
    (net (code "72") (name "unconnected-(IC1-GPB7-Pad8)") (class "Default")
      (node (ref "IC1") (pin "8") (pinfunction "GPB7_8") (pintype "bidirectional"))
    )
    (net (code "73") (name "unconnected-(IC1-INTA-Pad20)") (class "Default")
      (node (ref "IC1") (pin "20") (pinfunction "INTA_20") (pintype "output"))
    )
    (net (code "74") (name "unconnected-(IC1-INTB-Pad19)") (class "Default")
      (node (ref "IC1") (pin "19") (pinfunction "INTB_19") (pintype "output"))
    )
    (net (code "75") (name "unconnected-(U1-*D10-PadD10)") (class "Default")
      (node (ref "U1") (pin "D10") (pinfunction "*D10_D10") (pintype "bidirectional"))
    )
    (net (code "76") (name "unconnected-(U1-*D11-PadD11)") (class "Default")
      (node (ref "U1") (pin "D11") (pinfunction "*D11_D11") (pintype "bidirectional"))
    )
    (net (code "77") (name "unconnected-(U1-Pad3.3V)") (class "Default")
      (node (ref "U1") (pin "3.3V") (pinfunction "3.3V_3.3V") (pintype "bidirectional"))
    )
    (net (code "78") (name "unconnected-(U1-PadA1)") (class "Default")
      (node (ref "U1") (pin "A1") (pinfunction "A1_A1") (pintype "bidirectional"))
    )
    (net (code "79") (name "unconnected-(U1-PadA2)") (class "Default")
      (node (ref "U1") (pin "A2") (pinfunction "A2_A2") (pintype "bidirectional"))
    )
    (net (code "80") (name "unconnected-(U1-PadA3)") (class "Default")
      (node (ref "U1") (pin "A3") (pinfunction "A3_A3") (pintype "bidirectional"))
    )
    (net (code "81") (name "unconnected-(U1-PadAREF)") (class "Default")
      (node (ref "U1") (pin "AREF") (pinfunction "AREF_AREF") (pintype "bidirectional"))
    )
    (net (code "82") (name "unconnected-(U1-PadD4)") (class "Default")
      (node (ref "U1") (pin "D4") (pinfunction "D4_D4") (pintype "bidirectional"))
    )
    (net (code "83") (name "unconnected-(U1-PadD12)") (class "Default")
      (node (ref "U1") (pin "D12") (pinfunction "D12_D12") (pintype "bidirectional"))
    )
    (net (code "84") (name "unconnected-(U1-PadD13)") (class "Default")
      (node (ref "U1") (pin "D13") (pinfunction "D13_D13") (pintype "bidirectional"))
    )
    (net (code "85") (name "unconnected-(U1-PadRX)") (class "Default")
      (node (ref "U1") (pin "RX") (pinfunction "RX_RX") (pintype "bidirectional"))
    )
    (net (code "86") (name "unconnected-(U1-PadTX)") (class "Default")
      (node (ref "U1") (pin "TX") (pinfunction "TX_TX") (pintype "bidirectional"))
    )
  )
)
